# Fuel_Gauge.net
KiCad netlist of a schematic drawn in Altium Designer
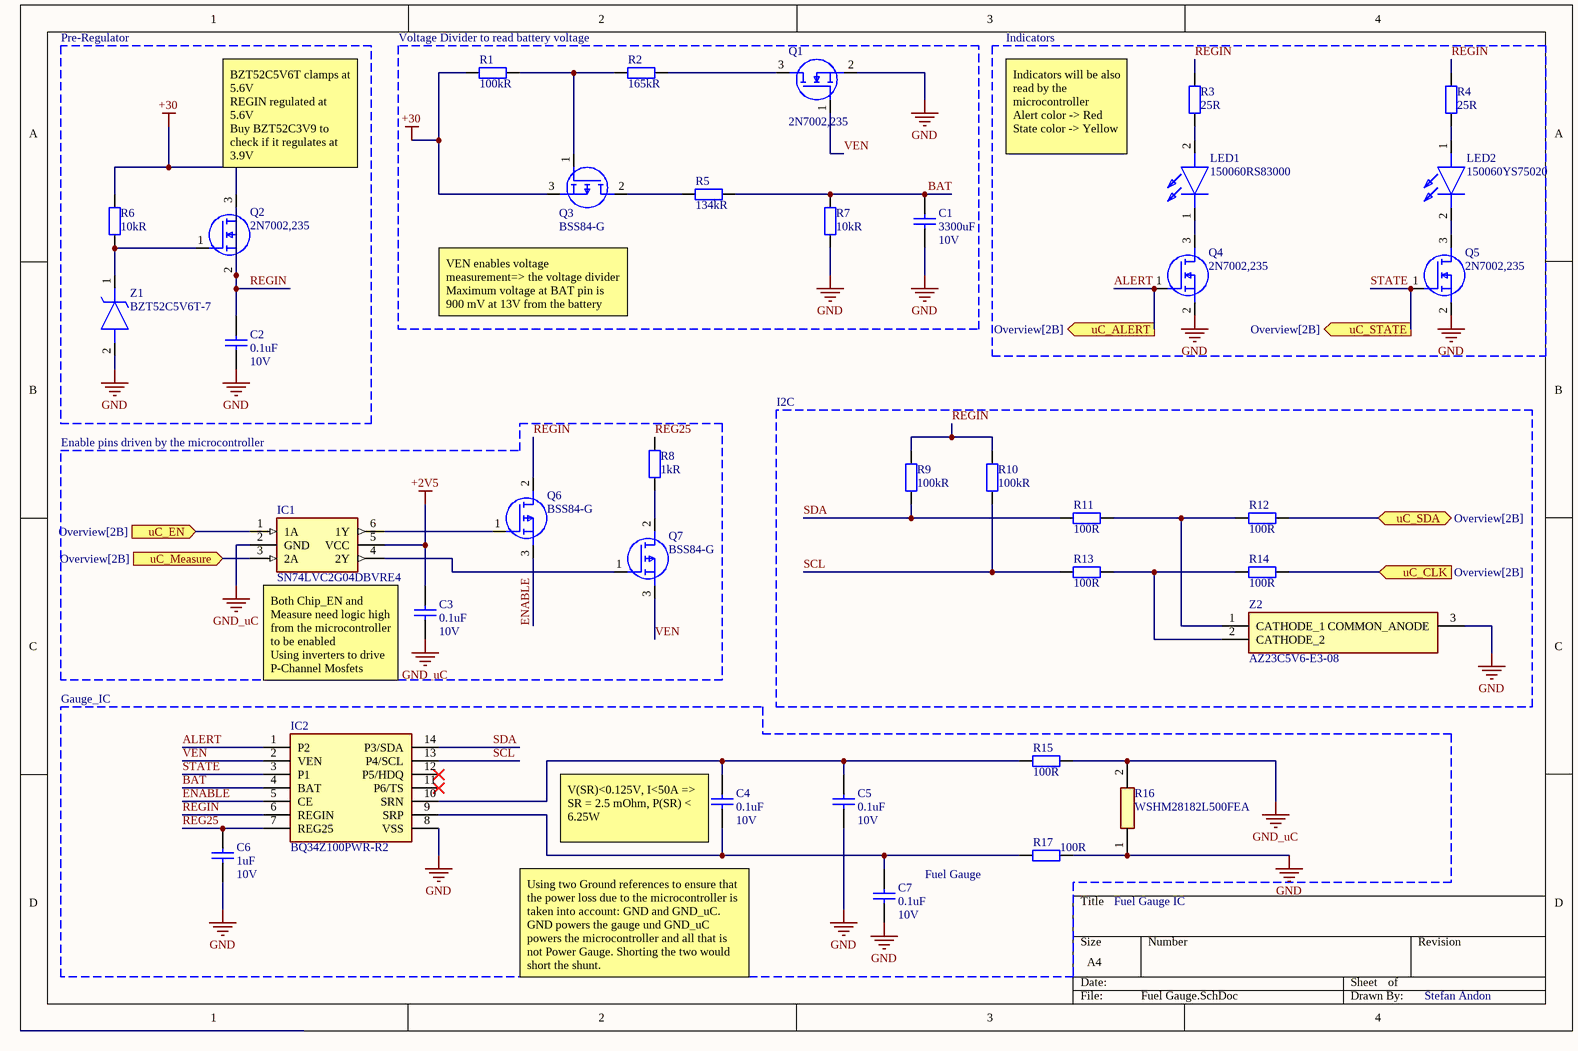
[diagram p0: Fuel Gauge.SchDoc]

(export (version "E")
  (design (tool "Eeschema 10.0.6"))
  (components
    (comp (ref "C1")
      (value "3300uF")
      (footprint "CAP_0603")
      (description "SMD Capacitor")
      (fields
        (field (name "TOLERANCE") "tbd")
        (field (name "VOLTAGE") "10V")
        (field (name "Comment") "Capacitor_SMD")
      )
      (libsource (lib "TUfast e") (part "SMD Capacitor"))
    )
    (comp (ref "C2")
      (value "0.1uF")
      (footprint "CAP_0603")
      (description "SMD Capacitor")
      (fields
        (field (name "TOLERANCE") "tbd")
        (field (name "VOLTAGE") "10V")
        (field (name "Comment") "Capacitor_SMD")
      )
      (libsource (lib "TUfast e") (part "SMD Capacitor"))
    )
    (comp (ref "C3")
      (value "0.1uF")
      (footprint "CAP_0603")
      (description "SMD Capacitor")
      (fields
        (field (name "TOLERANCE") "tbd")
        (field (name "VOLTAGE") "10V")
        (field (name "Comment") "Capacitor_SMD")
      )
      (libsource (lib "TUfast e") (part "SMD Capacitor"))
    )
    (comp (ref "C4")
      (value "0.1uF")
      (footprint "CAP_0603")
      (description "SMD Capacitor")
      (fields
        (field (name "TOLERANCE") "tbd")
        (field (name "VOLTAGE") "10V")
        (field (name "Comment") "Capacitor_SMD")
      )
      (libsource (lib "TUfast e") (part "SMD Capacitor"))
    )
    (comp (ref "C5")
      (value "0.1uF")
      (footprint "CAP_0603")
      (description "SMD Capacitor")
      (fields
        (field (name "TOLERANCE") "tbd")
        (field (name "VOLTAGE") "10V")
        (field (name "Comment") "Capacitor_SMD")
      )
      (libsource (lib "TUfast e") (part "SMD Capacitor"))
    )
    (comp (ref "C6")
      (value "1uF")
      (footprint "CAP_0603")
      (description "SMD Capacitor")
      (fields
        (field (name "TOLERANCE") "tbd")
        (field (name "VOLTAGE") "10V")
        (field (name "Comment") "Capacitor_SMD")
      )
      (libsource (lib "TUfast e") (part "SMD Capacitor"))
    )
    (comp (ref "C7")
      (value "0.1uF")
      (footprint "CAP_0603")
      (description "SMD Capacitor")
      (fields
        (field (name "TOLERANCE") "tbd")
        (field (name "VOLTAGE") "10V")
        (field (name "Comment") "Capacitor_SMD")
      )
      (libsource (lib "TUfast e") (part "SMD Capacitor"))
    )
    (comp (ref "IC1")
      (value "SN74LVC2G04DBVRE4")
      (footprint "SamacSys:SOT95P280X145-6N")
      (description "Integrated Circuit")
      (fields (field (name "MOUSER PART NUMBER") "595-SN74LVC2G04DBVRE"))
      (libsource (lib "*") (part "SN74LVC2G04DBVRE4"))
    )
    (comp (ref "IC2")
      (value "BQ34Z100PWR-R2")
      (footprint "SamacSys:SOP65P640X120-14N")
      (description "Integrated Circuit")
      (fields (field (name "MOUSER PART NUMBER") "595-BQ34Z100PWR-R2"))
      (libsource (lib "*") (part "BQ34Z100PWR-R2"))
    )
    (comp (ref "LED1")
      (value "150060RS83000")
      (footprint "SamacSys:LEDC1608X115N")
      (description "LED")
      (libsource (lib "*") (part "150060RS83000"))
    )
    (comp (ref "LED2")
      (value "150060YS75020")
      (footprint "SamacSys:150060YS75020")
      (description "LED")
      (fields (field (name "MOUSER PART NUMBER") "710-150060YS75020"))
      (libsource (lib "*") (part "150060YS75020"))
    )
    (comp (ref "Q1")
      (value "2N7002,235")
      (footprint "SamacSys:SOT95P230X110-3N")
      (description "MOSFET (N-Channel)")
      (fields (field (name "MOUSER PART NUMBER") "771-2N7002235"))
      (libsource (lib "*") (part "2N7002,235"))
    )
    (comp (ref "Q2")
      (value "2N7002,235")
      (footprint "SamacSys:SOT95P230X110-3N")
      (description "MOSFET (N-Channel)")
      (fields (field (name "MOUSER PART NUMBER") "771-2N7002235"))
      (libsource (lib "*") (part "2N7002,235"))
    )
    (comp (ref "Q3")
      (value "BSS84-G")
      (footprint "SamacSys:SOT95P240X120-3N")
      (description "MOSFET (P-Channel)")
      (fields (field (name "MOUSER PART NUMBER") "863-BSS84-G"))
      (libsource (lib "*") (part "BSS84-G"))
    )
    (comp (ref "Q4")
      (value "2N7002,235")
      (footprint "SamacSys:SOT95P230X110-3N")
      (description "MOSFET (N-Channel)")
      (fields (field (name "MOUSER PART NUMBER") "771-2N7002235"))
      (libsource (lib "*") (part "2N7002,235"))
    )
    (comp (ref "Q5")
      (value "2N7002,235")
      (footprint "SamacSys:SOT95P230X110-3N")
      (description "MOSFET (N-Channel)")
      (fields (field (name "MOUSER PART NUMBER") "771-2N7002235"))
      (libsource (lib "*") (part "2N7002,235"))
    )
    (comp (ref "Q6")
      (value "BSS84-G")
      (footprint "SamacSys:SOT95P240X120-3N")
      (description "MOSFET (P-Channel)")
      (fields (field (name "MOUSER PART NUMBER") "863-BSS84-G"))
      (libsource (lib "*") (part "BSS84-G"))
    )
    (comp (ref "Q7")
      (value "BSS84-G")
      (footprint "SamacSys:SOT95P240X120-3N")
      (description "MOSFET (P-Channel)")
      (fields (field (name "MOUSER PART NUMBER") "863-BSS84-G"))
      (libsource (lib "*") (part "BSS84-G"))
    )
    (comp (ref "R1")
      (value "100kR")
      (footprint "RES_0603")
      (fields
        (field (name "TOLERANCE") "tbd")
        (field (name "POWER") "7W")
        (field (name "Comment") "Resistor_SMD")
      )
      (libsource (lib "") (part "Resistor_3"))
    )
    (comp (ref "R2")
      (value "165kR")
      (footprint "RES_0603")
      (fields
        (field (name "TOLERANCE") "tbd")
        (field (name "POWER") "7W")
        (field (name "Comment") "Resistor_SMD")
      )
      (libsource (lib "") (part "Resistor_3"))
    )
    (comp (ref "R3")
      (value "25R")
      (footprint "RES_0603")
      (fields
        (field (name "TOLERANCE") "tbd")
        (field (name "POWER") "7W")
        (field (name "Comment") "Resistor_SMD")
      )
      (libsource (lib "TUfast e") (part "Resistor"))
    )
    (comp (ref "R4")
      (value "25R")
      (footprint "RES_0603")
      (fields
        (field (name "TOLERANCE") "tbd")
        (field (name "POWER") "7W")
        (field (name "Comment") "Resistor_SMD")
      )
      (libsource (lib "TUfast e") (part "Resistor"))
    )
    (comp (ref "R5")
      (value "134kR")
      (footprint "RES_0603")
      (fields
        (field (name "TOLERANCE") "tbd")
        (field (name "POWER") "7W")
        (field (name "Comment") "Resistor_SMD")
      )
      (libsource (lib "") (part "Resistor_3"))
    )
    (comp (ref "R6")
      (value "10kR")
      (footprint "RES_0603")
      (fields
        (field (name "TOLERANCE") "tbd")
        (field (name "POWER") "7W")
        (field (name "Comment") "Resistor_SMD")
      )
      (libsource (lib "") (part "Resistor_2"))
    )
    (comp (ref "R7")
      (value "10kR")
      (footprint "RES_0603")
      (fields
        (field (name "TOLERANCE") "tbd")
        (field (name "POWER") "7W")
        (field (name "Comment") "Resistor_SMD")
      )
      (libsource (lib "TUfast e") (part "Resistor"))
    )
    (comp (ref "R8")
      (value "1kR")
      (footprint "RES_0603")
      (fields
        (field (name "TOLERANCE") "tbd")
        (field (name "POWER") "7W")
        (field (name "Comment") "Resistor_SMD")
      )
      (libsource (lib "TUfast e") (part "Resistor"))
    )
    (comp (ref "R9")
      (value "100kR")
      (footprint "RES_0603")
      (fields
        (field (name "TOLERANCE") "tbd")
        (field (name "POWER") "7W")
        (field (name "Comment") "Resistor_SMD")
      )
      (libsource (lib "TUfast e") (part "Resistor"))
    )
    (comp (ref "R10")
      (value "100kR")
      (footprint "RES_0603")
      (fields
        (field (name "TOLERANCE") "tbd")
        (field (name "POWER") "7W")
        (field (name "Comment") "Resistor_SMD")
      )
      (libsource (lib "TUfast e") (part "Resistor"))
    )
    (comp (ref "R11")
      (value "100R")
      (footprint "RES_0603")
      (fields
        (field (name "TOLERANCE") "tbd")
        (field (name "POWER") "7W")
        (field (name "Comment") "Resistor_SMD")
      )
      (libsource (lib "") (part "Resistor_1"))
    )
    (comp (ref "R12")
      (value "100R")
      (footprint "RES_0603")
      (fields
        (field (name "TOLERANCE") "tbd")
        (field (name "POWER") "7W")
        (field (name "Comment") "Resistor_SMD")
      )
      (libsource (lib "") (part "Resistor_1"))
    )
    (comp (ref "R13")
      (value "100R")
      (footprint "RES_0603")
      (fields
        (field (name "TOLERANCE") "tbd")
        (field (name "POWER") "7W")
        (field (name "Comment") "Resistor_SMD")
      )
      (libsource (lib "") (part "Resistor_1"))
    )
    (comp (ref "R14")
      (value "100R")
      (footprint "RES_0603")
      (fields
        (field (name "TOLERANCE") "tbd")
        (field (name "POWER") "7W")
        (field (name "Comment") "Resistor_SMD")
      )
      (libsource (lib "") (part "Resistor_1"))
    )
    (comp (ref "R15")
      (value "100R")
      (footprint "RES_0603")
      (fields
        (field (name "TOLERANCE") "tbd")
        (field (name "POWER") "7W")
        (field (name "Comment") "Resistor_SMD")
      )
      (libsource (lib "") (part "Resistor_1"))
    )
    (comp (ref "R16")
      (value "WSHM28182L500FEA")
      (footprint "SamacSys:WSHM28182L500FEA")
      (description "Resistor")
      (fields (field (name "MOUSER PART NUMBER") "71-WSHM28182L500FEA"))
      (libsource (lib "*") (part "WSHM28182L500FEA"))
    )
    (comp (ref "R17")
      (value "100R")
      (footprint "RES_0603")
      (fields
        (field (name "TOLERANCE") "tbd")
        (field (name "POWER") "7W")
        (field (name "Comment") "Resistor_SMD")
      )
      (libsource (lib "") (part "Resistor_1"))
    )
    (comp (ref "Z1")
      (value "BZT52C5V6T-7")
      (footprint "SamacSys:BZT52C5V6T7")
      (description "Zener Diode")
      (fields (field (name "MOUSER PART NUMBER") "621-BZT52C5V6T-7"))
      (libsource (lib "*") (part "BZT52C5V6T-7"))
    )
    (comp (ref "Z2")
      (value "AZ23C5V6-E3-08")
      (footprint "SamacSys:SOT95P248X115-3N")
      (description "Zener Diode")
      (fields (field (name "MOUSER PART NUMBER") "78-AZ23C5V6-E3-08"))
      (libsource (lib "*") (part "AZ23C5V6-E3-08"))
    )
  )
  (nets
    (net (code "1") (name "+2V5") (class "Default")
      (node (ref "C3") (pin "2") (pinfunction "2_2") (pintype "passive"))
      (node (ref "IC1") (pin "5") (pinfunction "VCC_5") (pintype "power_in"))
    )
    (net (code "2") (name "+30") (class "Default")
      (node (ref "Q2") (pin "3") (pinfunction "D_3") (pintype "passive"))
      (node (ref "Q3") (pin "3") (pinfunction "S_3") (pintype "passive"))
      (node (ref "R1") (pin "1") (pinfunction "1_1") (pintype "passive"))
      (node (ref "R6") (pin "1") (pinfunction "1_1") (pintype "passive"))
    )
    (net (code "3") (name "/ALERT") (class "Default")
      (node (ref "IC2") (pin "1") (pinfunction "P2_1") (pintype "passive"))
      (node (ref "Q4") (pin "1") (pinfunction "G_1") (pintype "passive"))
    )
    (net (code "4") (name "/BAT") (class "Default")
      (node (ref "C1") (pin "2") (pinfunction "2_2") (pintype "passive"))
      (node (ref "IC2") (pin "4") (pinfunction "BAT_4") (pintype "passive"))
      (node (ref "R5") (pin "2") (pinfunction "2_2") (pintype "passive"))
      (node (ref "R7") (pin "2") (pinfunction "2_2") (pintype "passive"))
    )
    (net (code "5") (name "/ENABLE") (class "Default")
      (node (ref "IC2") (pin "5") (pinfunction "CE_5") (pintype "passive"))
      (node (ref "Q6") (pin "3") (pinfunction "S_3") (pintype "passive"))
    )
    (net (code "6") (name "/REG25") (class "Default")
      (node (ref "C6") (pin "2") (pinfunction "2_2") (pintype "passive"))
      (node (ref "IC2") (pin "7") (pinfunction "REG25_7") (pintype "passive"))
      (node (ref "R8") (pin "2") (pinfunction "2_2") (pintype "passive"))
    )
    (net (code "7") (name "/REGIN") (class "Default")
      (node (ref "C2") (pin "2") (pinfunction "2_2") (pintype "passive"))
      (node (ref "IC2") (pin "6") (pinfunction "REGIN_6") (pintype "passive"))
      (node (ref "Q2") (pin "2") (pinfunction "S_2") (pintype "passive"))
      (node (ref "Q6") (pin "2") (pinfunction "D_2") (pintype "passive"))
      (node (ref "R10") (pin "2") (pinfunction "2_2") (pintype "passive"))
      (node (ref "R3") (pin "2") (pinfunction "2_2") (pintype "passive"))
      (node (ref "R4") (pin "2") (pinfunction "2_2") (pintype "passive"))
      (node (ref "R9") (pin "2") (pinfunction "2_2") (pintype "passive"))
    )
    (net (code "8") (name "/SCL") (class "Default")
      (node (ref "IC2") (pin "13") (pinfunction "P4/SCL_13") (pintype "passive"))
      (node (ref "R10") (pin "1") (pinfunction "1_1") (pintype "passive"))
      (node (ref "R13") (pin "2") (pinfunction "2_2") (pintype "passive"))
    )
    (net (code "9") (name "/SDA") (class "Default")
      (node (ref "IC2") (pin "14") (pinfunction "P3/SDA_14") (pintype "passive"))
      (node (ref "R11") (pin "2") (pinfunction "2_2") (pintype "passive"))
      (node (ref "R9") (pin "1") (pinfunction "1_1") (pintype "passive"))
    )
    (net (code "10") (name "/STATE") (class "Default")
      (node (ref "IC2") (pin "3") (pinfunction "P1_3") (pintype "passive"))
      (node (ref "Q5") (pin "1") (pinfunction "G_1") (pintype "passive"))
    )
    (net (code "11") (name "/VEN") (class "Default")
      (node (ref "IC2") (pin "2") (pinfunction "VEN_2") (pintype "passive"))
      (node (ref "Q1") (pin "1") (pinfunction "G_1") (pintype "passive"))
      (node (ref "Q7") (pin "3") (pinfunction "S_3") (pintype "passive"))
    )
    (net (code "12") (name "/uC_CLK") (class "Default")
      (node (ref "R14") (pin "1") (pinfunction "1_1") (pintype "passive"))
    )
    (net (code "13") (name "/uC_EN") (class "Default")
      (node (ref "IC1") (pin "1") (pinfunction "1A_1") (pintype "input"))
    )
    (net (code "14") (name "/uC_Measure") (class "Default")
      (node (ref "IC1") (pin "3") (pinfunction "2A_3") (pintype "input"))
    )
    (net (code "15") (name "/uC_SDA") (class "Default")
      (node (ref "R12") (pin "1") (pinfunction "1_1") (pintype "passive"))
    )
    (net (code "16") (name "GND") (class "Default")
      (node (ref "C1") (pin "1") (pinfunction "1_1") (pintype "passive"))
      (node (ref "C2") (pin "1") (pinfunction "1_1") (pintype "passive"))
      (node (ref "C5") (pin "1") (pinfunction "1_1") (pintype "passive"))
      (node (ref "C6") (pin "1") (pinfunction "1_1") (pintype "passive"))
      (node (ref "C7") (pin "1") (pinfunction "1_1") (pintype "passive"))
      (node (ref "IC2") (pin "8") (pinfunction "VSS_8") (pintype "passive"))
      (node (ref "Q1") (pin "2") (pinfunction "S_2") (pintype "passive"))
      (node (ref "Q4") (pin "2") (pinfunction "S_2") (pintype "passive"))
      (node (ref "Q5") (pin "2") (pinfunction "S_2") (pintype "passive"))
      (node (ref "R16") (pin "1") (pinfunction "1_1") (pintype "passive"))
      (node (ref "R17") (pin "1") (pinfunction "1_1") (pintype "passive"))
      (node (ref "R7") (pin "1") (pinfunction "1_1") (pintype "passive"))
      (node (ref "Z1") (pin "2") (pinfunction "A_2") (pintype "passive"))
      (node (ref "Z2") (pin "3") (pinfunction "COMMON_ANODE_3") (pintype "passive"))
    )
    (net (code "17") (name "GND_uC") (class "Default")
      (node (ref "C3") (pin "1") (pinfunction "1_1") (pintype "passive"))
      (node (ref "IC1") (pin "2") (pinfunction "GND_2") (pintype "power_in"))
      (node (ref "R15") (pin "1") (pinfunction "1_1") (pintype "passive"))
      (node (ref "R16") (pin "2") (pinfunction "2_2") (pintype "passive"))
    )
    (net (code "18") (name "Net-(IC1-1Y)") (class "Default")
      (node (ref "IC1") (pin "6") (pinfunction "1Y_6") (pintype "output"))
      (node (ref "Q6") (pin "1") (pinfunction "G_1") (pintype "passive"))
    )
    (net (code "19") (name "Net-(IC1-2Y)") (class "Default")
      (node (ref "IC1") (pin "4") (pinfunction "2Y_4") (pintype "output"))
      (node (ref "Q7") (pin "1") (pinfunction "G_1") (pintype "passive"))
    )
    (net (code "20") (name "Net-(IC2-SRN)") (class "Default")
      (node (ref "C4") (pin "2") (pinfunction "2_2") (pintype "passive"))
      (node (ref "C5") (pin "2") (pinfunction "2_2") (pintype "passive"))
      (node (ref "IC2") (pin "10") (pinfunction "SRN_10") (pintype "passive"))
      (node (ref "R15") (pin "2") (pinfunction "2_2") (pintype "passive"))
    )
    (net (code "21") (name "Net-(IC2-SRP)") (class "Default")
      (node (ref "C4") (pin "1") (pinfunction "1_1") (pintype "passive"))
      (node (ref "C7") (pin "2") (pinfunction "2_2") (pintype "passive"))
      (node (ref "IC2") (pin "9") (pinfunction "SRP_9") (pintype "passive"))
      (node (ref "R17") (pin "2") (pinfunction "2_2") (pintype "passive"))
    )
    (net (code "22") (name "Net-(LED1-A)") (class "Default")
      (node (ref "LED1") (pin "2") (pinfunction "A_2") (pintype "passive"))
      (node (ref "R3") (pin "1") (pinfunction "1_1") (pintype "passive"))
    )
    (net (code "23") (name "Net-(LED1-K)") (class "Default")
      (node (ref "LED1") (pin "1") (pinfunction "K_1") (pintype "passive"))
      (node (ref "Q4") (pin "3") (pinfunction "D_3") (pintype "passive"))
    )
    (net (code "24") (name "Net-(LED2-A)") (class "Default")
      (node (ref "LED2") (pin "1") (pinfunction "A_1") (pintype "passive"))
      (node (ref "R4") (pin "1") (pinfunction "1_1") (pintype "passive"))
    )
    (net (code "25") (name "Net-(LED2-K)") (class "Default")
      (node (ref "LED2") (pin "2") (pinfunction "K_2") (pintype "passive"))
      (node (ref "Q5") (pin "3") (pinfunction "D_3") (pintype "passive"))
    )
    (net (code "26") (name "Net-(Q1-D)") (class "Default")
      (node (ref "Q1") (pin "3") (pinfunction "D_3") (pintype "passive"))
      (node (ref "R2") (pin "2") (pinfunction "2_2") (pintype "passive"))
    )
    (net (code "27") (name "Net-(Q2-G)") (class "Default")
      (node (ref "Q2") (pin "1") (pinfunction "G_1") (pintype "passive"))
      (node (ref "R6") (pin "2") (pinfunction "2_2") (pintype "passive"))
      (node (ref "Z1") (pin "1") (pinfunction "K_1") (pintype "passive"))
    )
    (net (code "28") (name "Net-(Q3-D)") (class "Default")
      (node (ref "Q3") (pin "2") (pinfunction "D_2") (pintype "passive"))
      (node (ref "R5") (pin "1") (pinfunction "1_1") (pintype "passive"))
    )
    (net (code "29") (name "Net-(Q3-G)") (class "Default")
      (node (ref "Q3") (pin "1") (pinfunction "G_1") (pintype "passive"))
      (node (ref "R1") (pin "2") (pinfunction "2_2") (pintype "passive"))
      (node (ref "R2") (pin "1") (pinfunction "1_1") (pintype "passive"))
    )
    (net (code "30") (name "Net-(Q7-D)") (class "Default")
      (node (ref "Q7") (pin "2") (pinfunction "D_2") (pintype "passive"))
      (node (ref "R8") (pin "1") (pinfunction "1_1") (pintype "passive"))
    )
    (net (code "31") (name "Net-(Z2-CATHODE_1)") (class "Default")
      (node (ref "R11") (pin "1") (pinfunction "1_1") (pintype "passive"))
      (node (ref "R12") (pin "2") (pinfunction "2_2") (pintype "passive"))
      (node (ref "Z2") (pin "1") (pinfunction "CATHODE_1_1") (pintype "passive"))
    )
    (net (code "32") (name "Net-(Z2-CATHODE_2)") (class "Default")
      (node (ref "R13") (pin "1") (pinfunction "1_1") (pintype "passive"))
      (node (ref "R14") (pin "2") (pinfunction "2_2") (pintype "passive"))
      (node (ref "Z2") (pin "2") (pinfunction "CATHODE_2_2") (pintype "passive"))
    )
    (net (code "33") (name "unconnected-(IC2-P5{slash}HDQ-Pad12)") (class "Default")
      (node (ref "IC2") (pin "12") (pinfunction "P5/HDQ_12") (pintype "passive+no_connect"))
    )
    (net (code "34") (name "unconnected-(IC2-P6{slash}TS-Pad11)") (class "Default")
      (node (ref "IC2") (pin "11") (pinfunction "P6/TS_11") (pintype "passive+no_connect"))
    )
  )
)
